# hub_moteurs.net
KiCad netlist of a schematic drawn in EAGLE
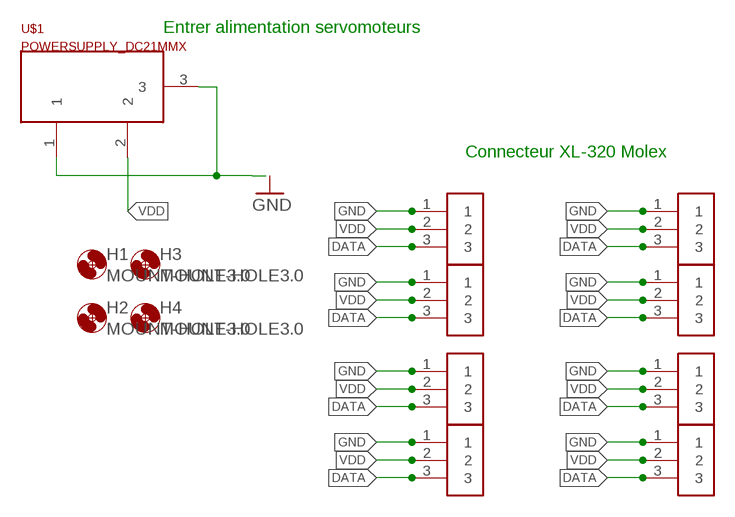
[diagram p0: schematic, sheet 1]

(export (version "E")
  (design (tool "Eeschema 10.0.6"))
  (components
    (comp (ref "H1")
      (value "MOUNT-HOLE3.0")
      (footprint "eagle-import:3,0")
      (libsource (lib "eagle-import") (part "MOUNT-HOLE3.0"))
    )
    (comp (ref "H2")
      (value "MOUNT-HOLE3.0")
      (footprint "eagle-import:3,0")
      (libsource (lib "eagle-import") (part "MOUNT-HOLE3.0"))
    )
    (comp (ref "H3")
      (value "MOUNT-HOLE3.0")
      (footprint "eagle-import:3,0")
      (libsource (lib "eagle-import") (part "MOUNT-HOLE3.0"))
    )
    (comp (ref "H4")
      (value "MOUNT-HOLE3.0")
      (footprint "eagle-import:3,0")
      (libsource (lib "eagle-import") (part "MOUNT-HOLE3.0"))
    )
    (comp (ref "U$1")
      (value "POWERSUPPLY_DC21MMX")
      (footprint "eagle-import:POWERSUPPLY_DC-21MM")
      (libsource (lib "eagle-import") (part "POWERSUPPLY_DC21MMX"))
    )
    (comp (ref "U$2")
      (value "CON_XL-320")
      (footprint "eagle-import:CON_XL-320")
      (libsource (lib "eagle-import") (part "CON_XL-3éà"))
    )
    (comp (ref "U$3")
      (value "CON_XL-320")
      (footprint "eagle-import:CON_XL-320")
      (libsource (lib "eagle-import") (part "CON_XL-3éà"))
    )
    (comp (ref "U$4")
      (value "CON_XL-320")
      (footprint "eagle-import:CON_XL-320")
      (libsource (lib "eagle-import") (part "CON_XL-3éà"))
    )
    (comp (ref "U$5")
      (value "CON_XL-320")
      (footprint "eagle-import:CON_XL-320")
      (libsource (lib "eagle-import") (part "CON_XL-3éà"))
    )
    (comp (ref "U$6")
      (value "CON_XL-320")
      (footprint "eagle-import:CON_XL-320")
      (libsource (lib "eagle-import") (part "CON_XL-3éà"))
    )
    (comp (ref "U$7")
      (value "CON_XL-320")
      (footprint "eagle-import:CON_XL-320")
      (libsource (lib "eagle-import") (part "CON_XL-3éà"))
    )
    (comp (ref "U$8")
      (value "CON_XL-320")
      (footprint "eagle-import:CON_XL-320")
      (libsource (lib "eagle-import") (part "CON_XL-3éà"))
    )
    (comp (ref "U$9")
      (value "CON_XL-320")
      (footprint "eagle-import:CON_XL-320")
      (libsource (lib "eagle-import") (part "CON_XL-3éà"))
    )
  )
  (nets
    (net (code "1") (name "DATA") (class "Default")
      (node (ref "U$2") (pin "3") (pinfunction "3_3") (pintype "bidirectional"))
      (node (ref "U$3") (pin "3") (pinfunction "3_3") (pintype "bidirectional"))
      (node (ref "U$4") (pin "3") (pinfunction "3_3") (pintype "bidirectional"))
      (node (ref "U$5") (pin "3") (pinfunction "3_3") (pintype "bidirectional"))
      (node (ref "U$6") (pin "3") (pinfunction "3_3") (pintype "bidirectional"))
      (node (ref "U$7") (pin "3") (pinfunction "3_3") (pintype "bidirectional"))
      (node (ref "U$8") (pin "3") (pinfunction "3_3") (pintype "bidirectional"))
      (node (ref "U$9") (pin "3") (pinfunction "3_3") (pintype "bidirectional"))
    )
    (net (code "2") (name "GND") (class "Default")
      (node (ref "U$1") (pin "1") (pinfunction "1_1") (pintype "power_in"))
      (node (ref "U$1") (pin "3") (pinfunction "3_3") (pintype "power_in"))
      (node (ref "U$2") (pin "1") (pinfunction "1_1") (pintype "bidirectional"))
      (node (ref "U$3") (pin "1") (pinfunction "1_1") (pintype "bidirectional"))
      (node (ref "U$4") (pin "1") (pinfunction "1_1") (pintype "bidirectional"))
      (node (ref "U$5") (pin "1") (pinfunction "1_1") (pintype "bidirectional"))
      (node (ref "U$6") (pin "1") (pinfunction "1_1") (pintype "bidirectional"))
      (node (ref "U$7") (pin "1") (pinfunction "1_1") (pintype "bidirectional"))
      (node (ref "U$8") (pin "1") (pinfunction "1_1") (pintype "bidirectional"))
      (node (ref "U$9") (pin "1") (pinfunction "1_1") (pintype "bidirectional"))
    )
    (net (code "3") (name "VDD") (class "Default")
      (node (ref "U$1") (pin "2") (pinfunction "2_2") (pintype "power_in"))
      (node (ref "U$2") (pin "2") (pinfunction "2_2") (pintype "bidirectional"))
      (node (ref "U$3") (pin "2") (pinfunction "2_2") (pintype "bidirectional"))
      (node (ref "U$4") (pin "2") (pinfunction "2_2") (pintype "bidirectional"))
      (node (ref "U$5") (pin "2") (pinfunction "2_2") (pintype "bidirectional"))
      (node (ref "U$6") (pin "2") (pinfunction "2_2") (pintype "bidirectional"))
      (node (ref "U$7") (pin "2") (pinfunction "2_2") (pintype "bidirectional"))
      (node (ref "U$8") (pin "2") (pinfunction "2_2") (pintype "bidirectional"))
      (node (ref "U$9") (pin "2") (pinfunction "2_2") (pintype "bidirectional"))
    )
  )
)
